# ife19_TS_Charger.net
KiCad netlist of a schematic drawn in Altium Designer
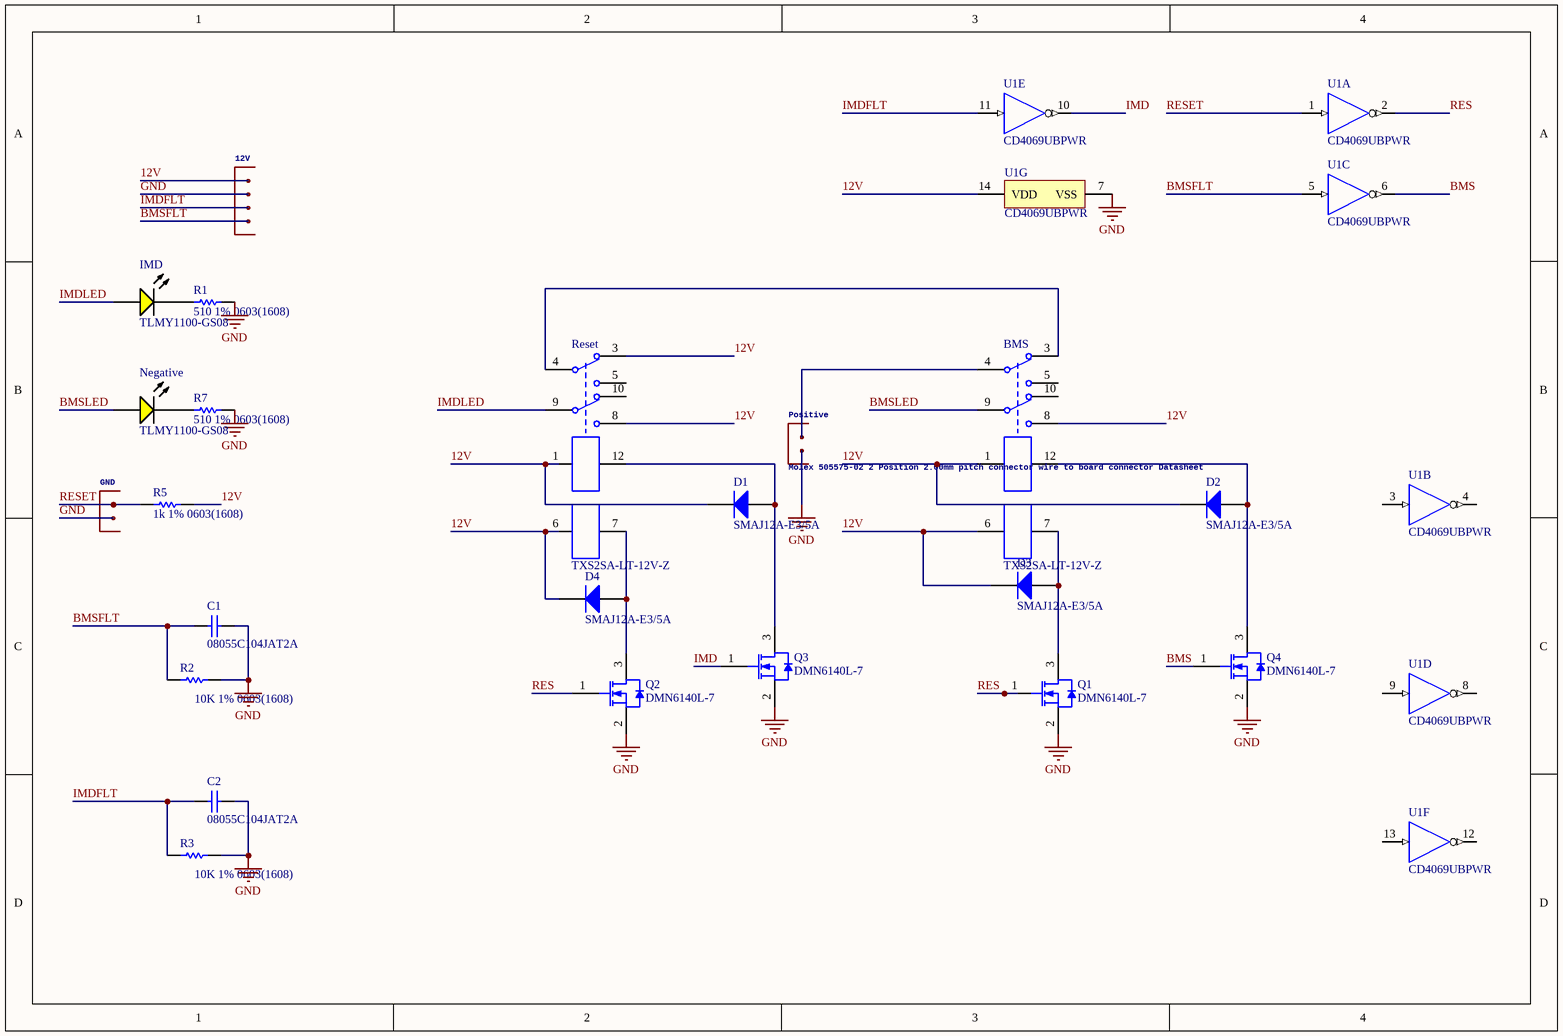
[diagram p0: ife19_TS_Charger.SchDoc]

(export (version "E")
  (design (tool "Eeschema 10.0.6"))
  (components
    (comp (ref "12V")
      (value "Molex 505575-04 4 Position 2.00mm pitch connector wire to board connector Datasheet")
      (footprint "505575-04")
      (fields (field (name "LIBRARYNAME") "MOLEX Micro-Lock"))
      (libsource (lib "MOLEX Micro-Lock") (part "505575-04"))
    )
    (comp (ref "BMS")
      (value "TXS2SA-LT-12V-Z")
      (footprint "PNSC-TXS2SA-L2_V")
      (description "Very High Sensitivity, Relay, 70 mW, 3 V, 10-Pin SMD, RoHS, Tape and Reel")
      (fields (field (name "MANUFACTURER") "Panasonic"))
      (libsource (lib "Altium Content Vault") (part "RELAY-DPDT-10"))
    )
    (comp (ref "C1")
      (value "08055C104JAT2A")
      (footprint "CAPC2013X94X50LL20T25")
      (description "Chip Capacitor, 0.1 uF, +/- 5%, 50 V, -55 to 125 degC, 0805 (2012 Metric), RoHS, Tape and Reel")
      (fields (field (name "TOLERANCE") "5%") (field (name "MANUFACTURER") "AVX"))
      (libsource (lib "Altium Content Vault") (part "CAP-NP-2"))
    )
    (comp (ref "C2")
      (value "08055C104JAT2A")
      (footprint "CAPC2013X94X50LL20T25")
      (description "Chip Capacitor, 0.1 uF, +/- 5%, 50 V, -55 to 125 degC, 0805 (2012 Metric), RoHS, Tape and Reel")
      (fields (field (name "TOLERANCE") "5%") (field (name "MANUFACTURER") "AVX"))
      (libsource (lib "Altium Content Vault") (part "CAP-NP-2"))
    )
    (comp (ref "D1")
      (value "SMAJ12A-E3/5A")
      (footprint "VISH-DO-214AC-2_M")
      (fields (field (name "MANUFACTURER") "Vishay Semiconductor"))
      (libsource (lib "Altium Content Vault") (part "VISH-K1A2-2"))
    )
    (comp (ref "D2")
      (value "SMAJ12A-E3/5A")
      (footprint "VISH-DO-214AC-2_M")
      (fields (field (name "MANUFACTURER") "Vishay Semiconductor"))
      (libsource (lib "Altium Content Vault") (part "VISH-K1A2-2"))
    )
    (comp (ref "D3")
      (value "SMAJ12A-E3/5A")
      (footprint "VISH-DO-214AC-2_M")
      (fields (field (name "MANUFACTURER") "Vishay Semiconductor"))
      (libsource (lib "Altium Content Vault") (part "VISH-K1A2-2"))
    )
    (comp (ref "D4")
      (value "SMAJ12A-E3/5A")
      (footprint "VISH-DO-214AC-2_M")
      (fields (field (name "MANUFACTURER") "Vishay Semiconductor"))
      (libsource (lib "Altium Content Vault") (part "VISH-K1A2-2"))
    )
    (comp (ref "GND")
      (value "Molex 505575-02 2 Position 2.00mm pitch connector wire to board connector Datasheet")
      (footprint "505575-02")
      (fields (field (name "LIBRARYNAME") "MOLEX Micro-Lock"))
      (libsource (lib "MOLEX Micro-Lock") (part "505575-02"))
    )
    (comp (ref "IMD")
      (value "TLMY1100-GS08")
      (footprint "VISH-TLMX1100-2_V")
      (description "Yellow LED, 20 mA, 2.1 V, -40 to 100 degC, 2-Pin SMD (0603), RoHS, Tape and Reel")
      (libsource (lib "Altium Content Vault") (part "LED-YELLOW-AK-2"))
    )
    (comp (ref "Negative")
      (value "TLMY1100-GS08")
      (footprint "VISH-TLMX1100-2_V")
      (description "Yellow LED, 20 mA, 2.1 V, -40 to 100 degC, 2-Pin SMD (0603), RoHS, Tape and Reel")
      (libsource (lib "Altium Content Vault") (part "LED-YELLOW-AK-2"))
    )
    (comp (ref "Positive")
      (value "Molex 505575-02 2 Position 2.00mm pitch connector wire to board connector Datasheet")
      (footprint "505575-02")
      (fields (field (name "LIBRARYNAME") "MOLEX Micro-Lock"))
      (libsource (lib "MOLEX Micro-Lock") (part "505575-02"))
    )
    (comp (ref "Q1")
      (value "DMN6140L-7")
      (footprint "FAIR-SOT23-3_V")
      (fields (field (name "TOLERANCE") "30ppm"))
      (libsource (lib "Altium Content Vault") (part "NEMOS-GSD-3"))
    )
    (comp (ref "Q2")
      (value "DMN6140L-7")
      (footprint "FAIR-SOT23-3_V")
      (fields (field (name "TOLERANCE") "30ppm"))
      (libsource (lib "Altium Content Vault") (part "NEMOS-GSD-3"))
    )
    (comp (ref "Q3")
      (value "DMN6140L-7")
      (footprint "FAIR-SOT23-3_V")
      (fields (field (name "TOLERANCE") "30ppm"))
      (libsource (lib "Altium Content Vault") (part "NEMOS-GSD-3"))
    )
    (comp (ref "Q4")
      (value "DMN6140L-7")
      (footprint "FAIR-SOT23-3_V")
      (fields (field (name "TOLERANCE") "30ppm"))
      (libsource (lib "Altium Content Vault") (part "NEMOS-GSD-3"))
    )
    (comp (ref "R1")
      (value "510 1% 0603(1608)")
      (footprint "RESC0603(1608)_L")
      (description "249K 0.1W 1% 0603 (1608 Metric)  SMD")
      (fields (field (name "POWER") "0.1 W") (field (name "TOLERANCE") "1 %"))
      (libsource (lib "Altium Content Vault") (part "RES"))
    )
    (comp (ref "R2")
      (value "10K 1% 0603(1608)")
      (footprint "RESC0603(1608)_L")
      (description "249K 0.1W 1% 0603 (1608 Metric)  SMD")
      (fields (field (name "POWER") "0.1 W") (field (name "TOLERANCE") "1 %"))
      (libsource (lib "Altium Content Vault") (part "RES"))
    )
    (comp (ref "R3")
      (value "10K 1% 0603(1608)")
      (footprint "RESC0603(1608)_L")
      (description "249K 0.1W 1% 0603 (1608 Metric)  SMD")
      (fields (field (name "POWER") "0.1 W") (field (name "TOLERANCE") "1 %"))
      (libsource (lib "Altium Content Vault") (part "RES"))
    )
    (comp (ref "R5")
      (value "1k 1% 0603(1608)")
      (footprint "RESC0603(1608)_L")
      (description "249K 0.1W 1% 0603 (1608 Metric)  SMD")
      (fields (field (name "POWER") "0.1 W") (field (name "TOLERANCE") "1 %"))
      (libsource (lib "Altium Content Vault") (part "RES"))
    )
    (comp (ref "R7")
      (value "510 1% 0603(1608)")
      (footprint "RESC0603(1608)_L")
      (description "249K 0.1W 1% 0603 (1608 Metric)  SMD")
      (fields (field (name "POWER") "0.1 W") (field (name "TOLERANCE") "1 %"))
      (libsource (lib "Altium Content Vault") (part "RES"))
    )
    (comp (ref "Reset")
      (value "TXS2SA-LT-12V-Z")
      (footprint "PNSC-TXS2SA-L2_V")
      (description "Very High Sensitivity, Relay, 70 mW, 3 V, 10-Pin SMD, RoHS, Tape and Reel")
      (fields (field (name "MANUFACTURER") "Panasonic"))
      (libsource (lib "Altium Content Vault") (part "RELAY-DPDT-10"))
    )
    (comp (ref "U1")
      (value "CD4069UBPWR")
      (footprint "PW0014A_N")
      (description "CMOS Hex Inverter, PW0014A, LARGE T&R")
      (fields
        (field (name "MANUFACTURER") "Texas Instruments")
        (field (name "GENERIC PART NUMBER") "CD4069UB")
      )
      (libsource (lib "Altium Content Vault") (part "TI-CD40XXXB-14"))
    )
  )
  (nets
    (net (code "1") (name "/12V") (class "Default")
      (node (ref "12V") (pin "1") (pinfunction "1_1") (pintype "passive"))
      (node (ref "BMS") (pin "1") (pinfunction "1_1") (pintype "passive"))
      (node (ref "BMS") (pin "6") (pinfunction "6_6") (pintype "passive"))
      (node (ref "BMS") (pin "8") (pinfunction "8_8") (pintype "passive"))
      (node (ref "D1") (pin "1") (pinfunction "K_1") (pintype "passive"))
      (node (ref "D2") (pin "1") (pinfunction "K_1") (pintype "passive"))
      (node (ref "D3") (pin "1") (pinfunction "K_1") (pintype "passive"))
      (node (ref "D4") (pin "1") (pinfunction "K_1") (pintype "passive"))
      (node (ref "R5") (pin "1") (pinfunction "1_1") (pintype "passive"))
      (node (ref "Reset") (pin "1") (pinfunction "1_1") (pintype "passive"))
      (node (ref "Reset") (pin "3") (pinfunction "3_3") (pintype "passive"))
      (node (ref "Reset") (pin "6") (pinfunction "6_6") (pintype "passive"))
      (node (ref "Reset") (pin "8") (pinfunction "8_8") (pintype "passive"))
      (node (ref "U1") (pin "14") (pinfunction "VDD_14") (pintype "power_in"))
    )
    (net (code "2") (name "/BMS") (class "Default")
      (node (ref "Q4") (pin "1") (pinfunction "G_1") (pintype "passive"))
      (node (ref "U1") (pin "6") (pinfunction "I=~{C}_6") (pintype "output"))
    )
    (net (code "3") (name "/BMSFLT") (class "Default")
      (node (ref "12V") (pin "4") (pinfunction "4_4") (pintype "passive"))
      (node (ref "C1") (pin "1") (pinfunction "1_1") (pintype "passive"))
      (node (ref "R2") (pin "2") (pinfunction "2_2") (pintype "passive"))
      (node (ref "U1") (pin "5") (pinfunction "C_5") (pintype "input"))
    )
    (net (code "4") (name "/BMSLED") (class "Default")
      (node (ref "BMS") (pin "9") (pinfunction "9_9") (pintype "passive"))
      (node (ref "Negative") (pin "1") (pinfunction "A_1") (pintype "passive"))
    )
    (net (code "5") (name "/IMD") (class "Default")
      (node (ref "Q3") (pin "1") (pinfunction "G_1") (pintype "passive"))
      (node (ref "U1") (pin "10") (pinfunction "K=~{E}_10") (pintype "output"))
    )
    (net (code "6") (name "/IMDFLT") (class "Default")
      (node (ref "12V") (pin "3") (pinfunction "3_3") (pintype "passive"))
      (node (ref "C2") (pin "1") (pinfunction "1_1") (pintype "passive"))
      (node (ref "R3") (pin "2") (pinfunction "2_2") (pintype "passive"))
      (node (ref "U1") (pin "11") (pinfunction "E_11") (pintype "input"))
    )
    (net (code "7") (name "/IMDLED") (class "Default")
      (node (ref "IMD") (pin "1") (pinfunction "A_1") (pintype "passive"))
      (node (ref "Reset") (pin "9") (pinfunction "9_9") (pintype "passive"))
    )
    (net (code "8") (name "/RES") (class "Default")
      (node (ref "Q1") (pin "1") (pinfunction "G_1") (pintype "passive"))
      (node (ref "Q2") (pin "1") (pinfunction "G_1") (pintype "passive"))
      (node (ref "U1") (pin "2") (pinfunction "G=~{A}_2") (pintype "output"))
    )
    (net (code "9") (name "/RESET") (class "Default")
      (node (ref "GND") (pin "1") (pinfunction "1_1") (pintype "passive"))
      (node (ref "R5") (pin "2") (pinfunction "2_2") (pintype "passive"))
      (node (ref "U1") (pin "1") (pinfunction "A_1") (pintype "input"))
    )
    (net (code "10") (name "GND") (class "Default")
      (node (ref "12V") (pin "2") (pinfunction "2_2") (pintype "passive"))
      (node (ref "C1") (pin "2") (pinfunction "2_2") (pintype "passive"))
      (node (ref "C2") (pin "2") (pinfunction "2_2") (pintype "passive"))
      (node (ref "GND") (pin "2") (pinfunction "2_2") (pintype "passive"))
      (node (ref "Positive") (pin "2") (pinfunction "2_2") (pintype "passive"))
      (node (ref "Q1") (pin "2") (pinfunction "S_2") (pintype "passive"))
      (node (ref "Q2") (pin "2") (pinfunction "S_2") (pintype "passive"))
      (node (ref "Q3") (pin "2") (pinfunction "S_2") (pintype "passive"))
      (node (ref "Q4") (pin "2") (pinfunction "S_2") (pintype "passive"))
      (node (ref "R1") (pin "1") (pinfunction "1_1") (pintype "passive"))
      (node (ref "R2") (pin "1") (pinfunction "1_1") (pintype "passive"))
      (node (ref "R3") (pin "1") (pinfunction "1_1") (pintype "passive"))
      (node (ref "R7") (pin "1") (pinfunction "1_1") (pintype "passive"))
      (node (ref "U1") (pin "7") (pinfunction "VSS_7") (pintype "power_in"))
    )
    (net (code "11") (name "Net-(BMS-Pad3)") (class "Default")
      (node (ref "BMS") (pin "3") (pinfunction "3_3") (pintype "passive"))
      (node (ref "Reset") (pin "4") (pinfunction "4_4") (pintype "passive"))
    )
    (net (code "12") (name "Net-(BMS-Pad4)") (class "Default")
      (node (ref "BMS") (pin "4") (pinfunction "4_4") (pintype "passive"))
      (node (ref "Positive") (pin "1") (pinfunction "1_1") (pintype "passive"))
    )
    (net (code "13") (name "Net-(D1-A)") (class "Default")
      (node (ref "D1") (pin "2") (pinfunction "A_2") (pintype "passive"))
      (node (ref "Q3") (pin "3") (pinfunction "D_3") (pintype "passive"))
      (node (ref "Reset") (pin "12") (pinfunction "12_12") (pintype "passive"))
    )
    (net (code "14") (name "Net-(D2-A)") (class "Default")
      (node (ref "BMS") (pin "12") (pinfunction "12_12") (pintype "passive"))
      (node (ref "D2") (pin "2") (pinfunction "A_2") (pintype "passive"))
      (node (ref "Q4") (pin "3") (pinfunction "D_3") (pintype "passive"))
    )
    (net (code "15") (name "Net-(D3-A)") (class "Default")
      (node (ref "BMS") (pin "7") (pinfunction "7_7") (pintype "passive"))
      (node (ref "D3") (pin "2") (pinfunction "A_2") (pintype "passive"))
      (node (ref "Q1") (pin "3") (pinfunction "D_3") (pintype "passive"))
    )
    (net (code "16") (name "Net-(D4-A)") (class "Default")
      (node (ref "D4") (pin "2") (pinfunction "A_2") (pintype "passive"))
      (node (ref "Q2") (pin "3") (pinfunction "D_3") (pintype "passive"))
      (node (ref "Reset") (pin "7") (pinfunction "7_7") (pintype "passive"))
    )
    (net (code "17") (name "Net-(IMD-K)") (class "Default")
      (node (ref "IMD") (pin "2") (pinfunction "K_2") (pintype "passive"))
      (node (ref "R1") (pin "2") (pinfunction "2_2") (pintype "passive"))
    )
    (net (code "18") (name "Net-(Negative-K)") (class "Default")
      (node (ref "Negative") (pin "2") (pinfunction "K_2") (pintype "passive"))
      (node (ref "R7") (pin "2") (pinfunction "2_2") (pintype "passive"))
    )
    (net (code "19") (name "unconnected-(BMS-Pad5)") (class "Default")
      (node (ref "BMS") (pin "5") (pinfunction "5_5") (pintype "passive"))
    )
    (net (code "20") (name "unconnected-(BMS-Pad10)") (class "Default")
      (node (ref "BMS") (pin "10") (pinfunction "10_10") (pintype "passive"))
    )
    (net (code "21") (name "unconnected-(Reset-Pad5)") (class "Default")
      (node (ref "Reset") (pin "5") (pinfunction "5_5") (pintype "passive"))
    )
    (net (code "22") (name "unconnected-(Reset-Pad10)") (class "Default")
      (node (ref "Reset") (pin "10") (pinfunction "10_10") (pintype "passive"))
    )
    (net (code "23") (name "unconnected-(U1B-B-Pad3)") (class "Default")
      (node (ref "U1") (pin "3") (pinfunction "B_3") (pintype "input"))
    )
    (net (code "24") (name "unconnected-(U1B-H=~{B}-Pad4)") (class "Default")
      (node (ref "U1") (pin "4") (pinfunction "H=~{B}_4") (pintype "output"))
    )
    (net (code "25") (name "unconnected-(U1D-D-Pad9)") (class "Default")
      (node (ref "U1") (pin "9") (pinfunction "D_9") (pintype "input"))
    )
    (net (code "26") (name "unconnected-(U1D-J=~{D}-Pad8)") (class "Default")
      (node (ref "U1") (pin "8") (pinfunction "J=~{D}_8") (pintype "output"))
    )
    (net (code "27") (name "unconnected-(U1F-F-Pad13)") (class "Default")
      (node (ref "U1") (pin "13") (pinfunction "F_13") (pintype "input"))
    )
    (net (code "28") (name "unconnected-(U1F-L=~{F}-Pad12)") (class "Default")
      (node (ref "U1") (pin "12") (pinfunction "L=~{F}_12") (pintype "output"))
    )
  )
)
